# HW1_BeverlyYee_u0770041.net
KiCad netlist of a schematic drawn in EAGLE
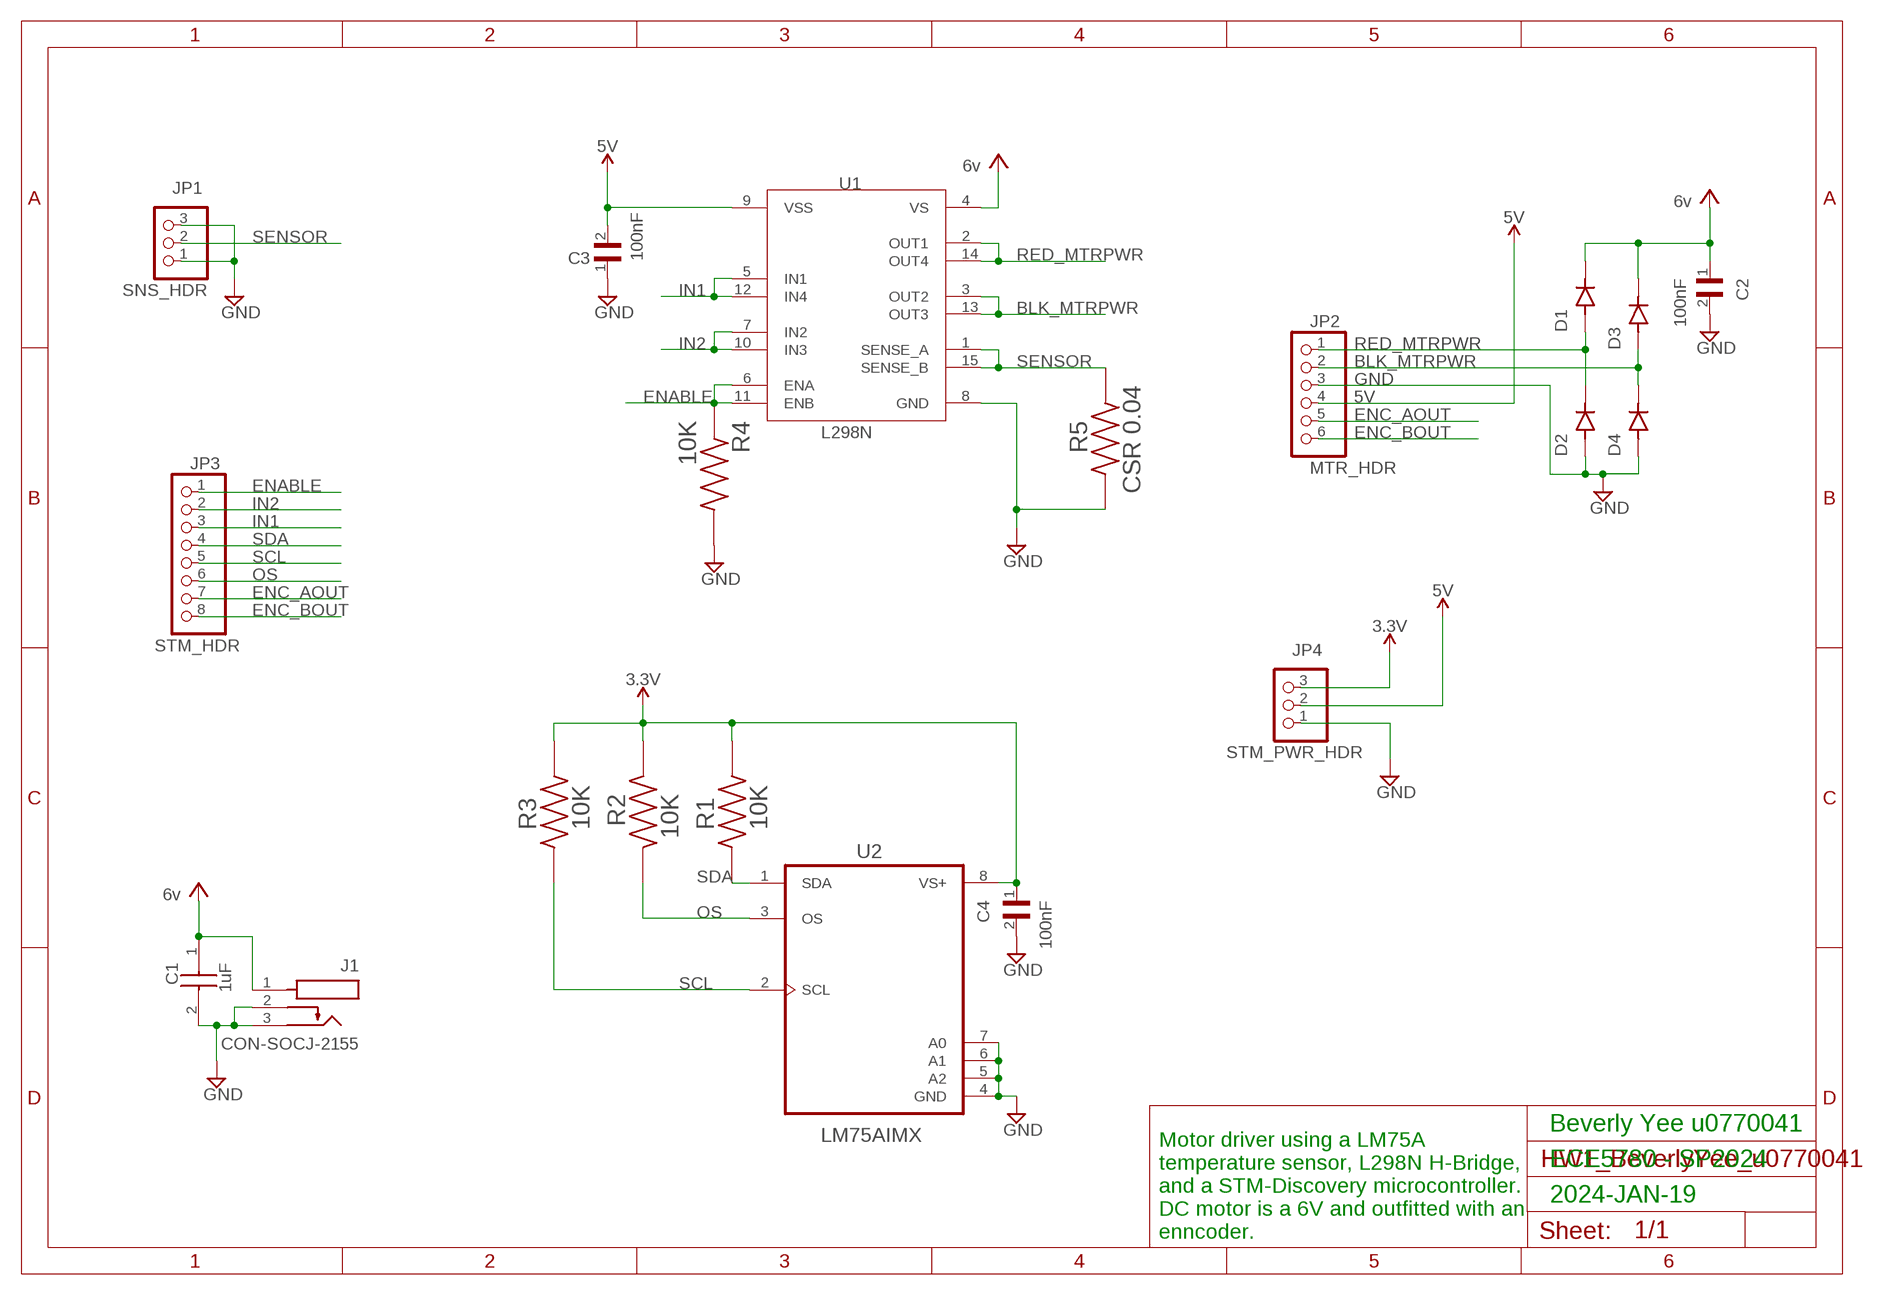
[diagram p0: schematic, sheet 1]

(export (version "E")
  (design (tool "Eeschema 10.0.6"))
  (components
    (comp (ref "C1")
      (value "1uF")
      (footprint "eagle-import:CAPPRD200W50D525H1250")
      (fields
        (field (name "MANUFACTURER_PART_NUMBER") "REA010M2CBK-0511P")
        (field (name "MOUSER_PART_NUMBER") "140-REA1R0M2CBK0511P")
      )
      (libsource (lib "eagle-import") (part "REA010M2CBK-0511P"))
    )
    (comp (ref "C2")
      (value "100nF")
      (footprint "eagle-import:CAPC3216X88N")
      (fields
        (field (name "DIGIKEY_PART_NUMBER") "399-C1206C104K5RAC7800TR-ND")
        (field (name "MF") "KEMET")
        (field (name "MP") "C1206C104K5RAC7800")
      )
      (libsource (lib "eagle-import") (part "C1206C104K5RAC7800"))
    )
    (comp (ref "C3")
      (value "100nF")
      (footprint "eagle-import:CAPC3216X88N")
      (fields
        (field (name "DIGIKEY_PART_NUMBER") "399-C1206C104K5RAC7800TR-ND")
        (field (name "MF") "KEMET")
        (field (name "MP") "C1206C104K5RAC7800")
      )
      (libsource (lib "eagle-import") (part "C1206C104K5RAC7800"))
    )
    (comp (ref "C4")
      (value "100nF")
      (footprint "eagle-import:CAPC3216X88N")
      (fields
        (field (name "DIGIKEY_PART_NUMBER") "399-C1206C104K5RAC7800TR-ND")
        (field (name "MF") "KEMET")
        (field (name "MP") "C1206C104K5RAC7800")
      )
      (libsource (lib "eagle-import") (part "C1206C104K5RAC7800"))
    )
    (comp (ref "D1")
      (value "RS2AA_R3G")
      (footprint "eagle-import:DIOM4325X250N")
      (fields
        (field (name "DIGIKEY_PART_NUMBER") "RS2AAR3GTR-ND")
        (field (name "MF") "Taiwan Semiconductor")
        (field (name "MP") "RS2AA R3G")
      )
      (libsource (lib "eagle-import") (part "RS2AA_R3G"))
    )
    (comp (ref "D2")
      (value "RS2AA_R3G")
      (footprint "eagle-import:DIOM4325X250N")
      (fields
        (field (name "DIGIKEY_PART_NUMBER") "RS2AAR3GTR-ND")
        (field (name "MF") "Taiwan Semiconductor")
        (field (name "MP") "RS2AA R3G")
      )
      (libsource (lib "eagle-import") (part "RS2AA_R3G"))
    )
    (comp (ref "D3")
      (value "RS2AA_R3G")
      (footprint "eagle-import:DIOM4325X250N")
      (fields
        (field (name "DIGIKEY_PART_NUMBER") "RS2AAR3GTR-ND")
        (field (name "MF") "Taiwan Semiconductor")
        (field (name "MP") "RS2AA R3G")
      )
      (libsource (lib "eagle-import") (part "RS2AA_R3G"))
    )
    (comp (ref "D4")
      (value "RS2AA_R3G")
      (footprint "eagle-import:DIOM4325X250N")
      (fields
        (field (name "DIGIKEY_PART_NUMBER") "RS2AAR3GTR-ND")
        (field (name "MF") "Taiwan Semiconductor")
        (field (name "MP") "RS2AA R3G")
      )
      (libsource (lib "eagle-import") (part "RS2AA_R3G"))
    )
    (comp (ref "J1")
      (value "CON-SOCJ-2155")
      (footprint "eagle-import:GRAVITECH_CON-SOCJ-2155")
      (fields (field (name "MF") "Gravitech"))
      (libsource (lib "eagle-import") (part "CON-SOCJ-2155"))
    )
    (comp (ref "JP1")
      (value "SNS_HDR")
      (footprint "eagle-import:1X03")
      (libsource (lib "eagle-import") (part "PINHD-1X3"))
    )
    (comp (ref "JP2")
      (value "MTR_HDR")
      (footprint "eagle-import:1X06")
      (libsource (lib "eagle-import") (part "PINHD-1X6"))
    )
    (comp (ref "JP3")
      (value "STM_HDR")
      (footprint "eagle-import:1X08")
      (libsource (lib "eagle-import") (part "PINHD-1X8"))
    )
    (comp (ref "JP4")
      (value "STM_PWR_HDR")
      (footprint "eagle-import:1X03")
      (libsource (lib "eagle-import") (part "PINHD-1X3"))
    )
    (comp (ref "R1")
      (value "10K")
      (footprint "eagle-import:RESC3116X65N")
      (fields
        (field (name "DIGIKEY_PART_NUMBER") "311-10KERTR-ND")
        (field (name "MF") "Yageo")
        (field (name "MP") "RC1206JR-0710KL")
      )
      (libsource (lib "eagle-import") (part "RC1206JR-0710KL"))
    )
    (comp (ref "R2")
      (value "10K")
      (footprint "eagle-import:RESC3116X65N")
      (fields
        (field (name "DIGIKEY_PART_NUMBER") "311-10KERTR-ND")
        (field (name "MF") "Yageo")
        (field (name "MP") "RC1206JR-0710KL")
      )
      (libsource (lib "eagle-import") (part "RC1206JR-0710KL"))
    )
    (comp (ref "R3")
      (value "10K")
      (footprint "eagle-import:RESC3116X65N")
      (fields
        (field (name "DIGIKEY_PART_NUMBER") "311-10KERTR-ND")
        (field (name "MF") "Yageo")
        (field (name "MP") "RC1206JR-0710KL")
      )
      (libsource (lib "eagle-import") (part "RC1206JR-0710KL"))
    )
    (comp (ref "R4")
      (value "10K")
      (footprint "eagle-import:RESC3116X65N")
      (fields
        (field (name "DIGIKEY_PART_NUMBER") "311-10KERTR-ND")
        (field (name "MF") "Yageo")
        (field (name "MP") "RC1206JR-0710KL")
      )
      (libsource (lib "eagle-import") (part "RC1206JR-0710KL"))
    )
    (comp (ref "R5")
      (value "CSR 0.04")
      (footprint "eagle-import:RESC3116X65N")
      (fields
        (field (name "DIGIKEY_PART_NUMBER") "311-.04LWTR-ND")
        (field (name "MF") "Yageo")
        (field (name "MP") "RL1206FR-070R04L")
      )
      (libsource (lib "eagle-import") (part "RL1206FR-070R04L"))
    )
    (comp (ref "U1")
      (value "L298N")
      (footprint "eagle-import:TO127P2020X500X2100-15")
      (fields (field (name "MF") "STMicroelectronics"))
      (libsource (lib "eagle-import") (part "L298N"))
    )
    (comp (ref "U2")
      (value "LM75AIMX")
      (footprint "eagle-import:SOIC127P599X175-8N")
      (fields
        (field (name "MF") "Texas Instruments")
        (field (name "MP") "LM75AIMX/NOPB")
        (field (name "COMPONENT") "TMP_SNSR")
      )
      (libsource (lib "eagle-import") (part "LM75AIMX/NOPB"))
    )
  )
  (nets
    (net (code "1") (name "/BLK_MTRPWR") (class "Default")
      (node (ref "D3") (pin "A") (pinfunction "A_A") (pintype "passive"))
      (node (ref "D4") (pin "C") (pinfunction "K_C") (pintype "passive"))
      (node (ref "JP2") (pin "2") (pinfunction "2_2") (pintype "passive"))
      (node (ref "U1") (pin "13") (pinfunction "OUT3_13") (pintype "output"))
      (node (ref "U1") (pin "3") (pinfunction "OUT2_3") (pintype "output"))
    )
    (net (code "2") (name "/ENABLE") (class "Default")
      (node (ref "JP3") (pin "1") (pinfunction "1_1") (pintype "passive"))
      (node (ref "R4") (pin "1") (pinfunction "1_1") (pintype "passive"))
      (node (ref "U1") (pin "11") (pinfunction "ENB_11") (pintype "input"))
      (node (ref "U1") (pin "6") (pinfunction "ENA_6") (pintype "input"))
    )
    (net (code "3") (name "/ENC_AOUT") (class "Default")
      (node (ref "JP2") (pin "5") (pinfunction "5_5") (pintype "passive"))
      (node (ref "JP3") (pin "7") (pinfunction "7_7") (pintype "passive"))
    )
    (net (code "4") (name "/ENC_BOUT") (class "Default")
      (node (ref "JP2") (pin "6") (pinfunction "6_6") (pintype "passive"))
      (node (ref "JP3") (pin "8") (pinfunction "8_8") (pintype "passive"))
    )
    (net (code "5") (name "/IN1") (class "Default")
      (node (ref "JP3") (pin "3") (pinfunction "3_3") (pintype "passive"))
      (node (ref "U1") (pin "12") (pinfunction "IN4_12") (pintype "input"))
      (node (ref "U1") (pin "5") (pinfunction "IN1_5") (pintype "input"))
    )
    (net (code "6") (name "/IN2") (class "Default")
      (node (ref "JP3") (pin "2") (pinfunction "2_2") (pintype "passive"))
      (node (ref "U1") (pin "10") (pinfunction "IN3_10") (pintype "input"))
      (node (ref "U1") (pin "7") (pinfunction "IN2_7") (pintype "input"))
    )
    (net (code "7") (name "/OS") (class "Default")
      (node (ref "JP3") (pin "6") (pinfunction "6_6") (pintype "passive"))
      (node (ref "R2") (pin "2") (pinfunction "2_2") (pintype "passive"))
      (node (ref "U2") (pin "3") (pinfunction "OS_3") (pintype "bidirectional"))
    )
    (net (code "8") (name "/RED_MTRPWR") (class "Default")
      (node (ref "D1") (pin "A") (pinfunction "A_A") (pintype "passive"))
      (node (ref "D2") (pin "C") (pinfunction "K_C") (pintype "passive"))
      (node (ref "JP2") (pin "1") (pinfunction "1_1") (pintype "passive"))
      (node (ref "U1") (pin "14") (pinfunction "OUT4_14") (pintype "output"))
      (node (ref "U1") (pin "2") (pinfunction "OUT1_2") (pintype "output"))
    )
    (net (code "9") (name "/SCL") (class "Default")
      (node (ref "JP3") (pin "5") (pinfunction "5_5") (pintype "passive"))
      (node (ref "R3") (pin "1") (pinfunction "1_1") (pintype "passive"))
      (node (ref "U2") (pin "2") (pinfunction "SCL_2") (pintype "input"))
    )
    (net (code "10") (name "/SDA") (class "Default")
      (node (ref "JP3") (pin "4") (pinfunction "4_4") (pintype "passive"))
      (node (ref "R1") (pin "1") (pinfunction "1_1") (pintype "passive"))
      (node (ref "U2") (pin "1") (pinfunction "SDA_1") (pintype "bidirectional"))
    )
    (net (code "11") (name "/SENSOR") (class "Default")
      (node (ref "JP1") (pin "2") (pinfunction "2_2") (pintype "passive"))
      (node (ref "R5") (pin "1") (pinfunction "1_1") (pintype "passive"))
      (node (ref "U1") (pin "1") (pinfunction "SENSE_A_1") (pintype "passive"))
      (node (ref "U1") (pin "15") (pinfunction "SENSE_B_15") (pintype "passive"))
    )
    (net (code "12") (name "3.3V") (class "Default")
      (node (ref "C4") (pin "1") (pinfunction "1_1") (pintype "passive"))
      (node (ref "JP4") (pin "3") (pinfunction "3_3") (pintype "passive"))
      (node (ref "R1") (pin "2") (pinfunction "2_2") (pintype "passive"))
      (node (ref "R2") (pin "1") (pinfunction "1_1") (pintype "passive"))
      (node (ref "R3") (pin "2") (pinfunction "2_2") (pintype "passive"))
      (node (ref "U2") (pin "8") (pinfunction "VS+_8") (pintype "power_in"))
    )
    (net (code "13") (name "5V") (class "Default")
      (node (ref "C3") (pin "2") (pinfunction "2_2") (pintype "passive"))
      (node (ref "JP2") (pin "4") (pinfunction "4_4") (pintype "passive"))
      (node (ref "JP4") (pin "2") (pinfunction "2_2") (pintype "passive"))
      (node (ref "U1") (pin "9") (pinfunction "VSS_9") (pintype "input"))
    )
    (net (code "14") (name "GND") (class "Default")
      (node (ref "C1") (pin "2") (pinfunction "-_2") (pintype "bidirectional"))
      (node (ref "C2") (pin "2") (pinfunction "2_2") (pintype "passive"))
      (node (ref "C3") (pin "1") (pinfunction "1_1") (pintype "passive"))
      (node (ref "C4") (pin "2") (pinfunction "2_2") (pintype "passive"))
      (node (ref "D2") (pin "A") (pinfunction "A_A") (pintype "passive"))
      (node (ref "D4") (pin "A") (pinfunction "A_A") (pintype "passive"))
      (node (ref "J1") (pin "2") (pinfunction "2_2") (pintype "passive"))
      (node (ref "J1") (pin "3") (pinfunction "3_3") (pintype "passive"))
      (node (ref "JP1") (pin "1") (pinfunction "1_1") (pintype "passive"))
      (node (ref "JP1") (pin "3") (pinfunction "3_3") (pintype "passive"))
      (node (ref "JP2") (pin "3") (pinfunction "3_3") (pintype "passive"))
      (node (ref "JP4") (pin "1") (pinfunction "1_1") (pintype "passive"))
      (node (ref "R4") (pin "2") (pinfunction "2_2") (pintype "passive"))
      (node (ref "R5") (pin "2") (pinfunction "2_2") (pintype "passive"))
      (node (ref "U1") (pin "8") (pinfunction "GND_8") (pintype "power_in"))
      (node (ref "U2") (pin "4") (pinfunction "GND_4") (pintype "power_in"))
      (node (ref "U2") (pin "5") (pinfunction "A2_5") (pintype "bidirectional"))
      (node (ref "U2") (pin "6") (pinfunction "A1_6") (pintype "bidirectional"))
      (node (ref "U2") (pin "7") (pinfunction "A0_7") (pintype "bidirectional"))
    )
    (net (code "15") (name "VCC") (class "Default")
      (node (ref "C1") (pin "1") (pinfunction "+_1") (pintype "bidirectional"))
      (node (ref "C2") (pin "1") (pinfunction "1_1") (pintype "passive"))
      (node (ref "D1") (pin "C") (pinfunction "K_C") (pintype "passive"))
      (node (ref "D3") (pin "C") (pinfunction "K_C") (pintype "passive"))
      (node (ref "J1") (pin "1") (pinfunction "1_1") (pintype "passive"))
      (node (ref "U1") (pin "4") (pinfunction "VS_4") (pintype "power_in"))
    )
  )
)
